# moids2_0_1power.net
KiCad netlist of a schematic drawn in EAGLE
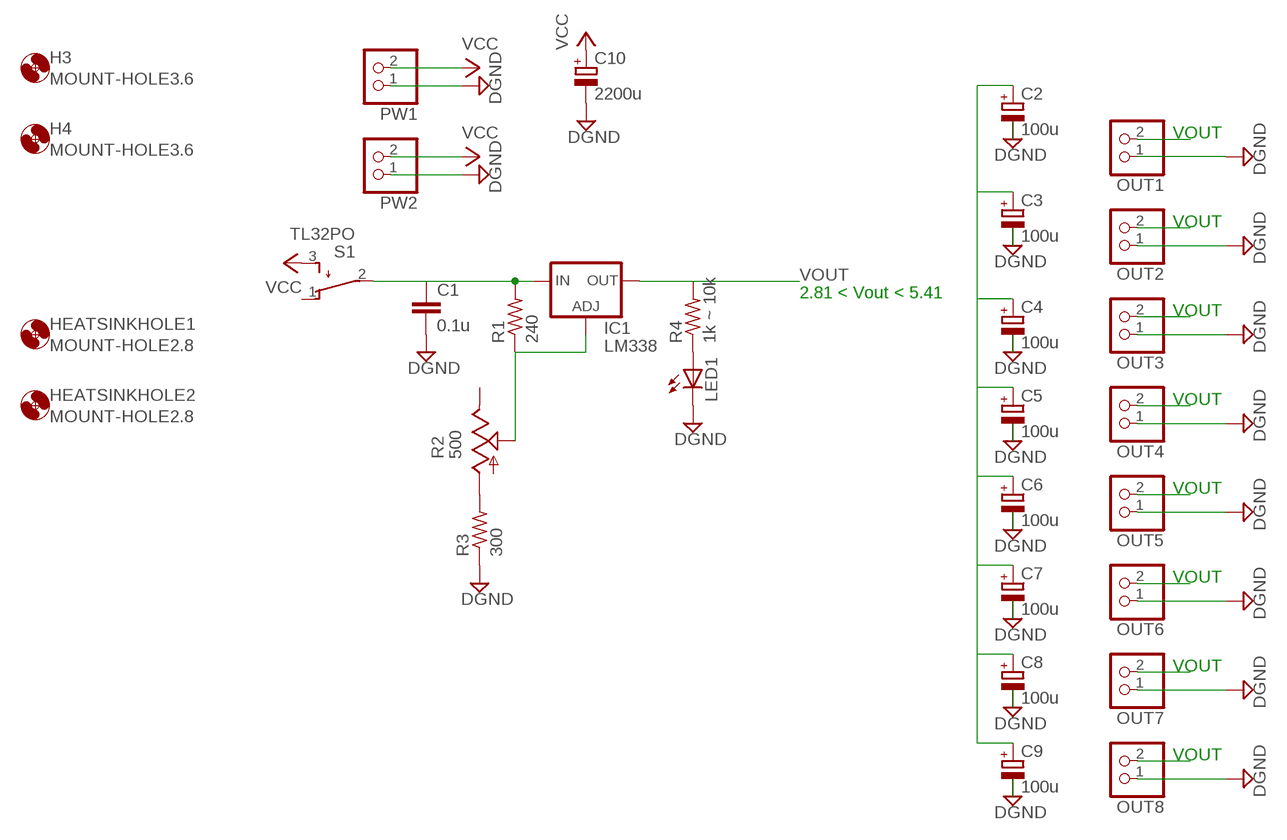
[diagram p0: schematic, sheet 1]

(export (version "E")
  (design (tool "Eeschema 10.0.6"))
  (components
    (comp (ref "C1")
      (value "0.1u")
      (footprint "eagle-import:C025-024X044")
      (libsource (lib "eagle-import") (part "C-EU025-024X044"))
    )
    (comp (ref "C2")
      (value "100u")
      (footprint "eagle-import:E2,5-5")
      (libsource (lib "eagle-import") (part "CPOL-EUE2.5-5"))
    )
    (comp (ref "C3")
      (value "100u")
      (footprint "eagle-import:E2,5-5")
      (libsource (lib "eagle-import") (part "CPOL-EUE2.5-5"))
    )
    (comp (ref "C4")
      (value "100u")
      (footprint "eagle-import:E2,5-5")
      (libsource (lib "eagle-import") (part "CPOL-EUE2.5-5"))
    )
    (comp (ref "C5")
      (value "100u")
      (footprint "eagle-import:E2,5-5")
      (libsource (lib "eagle-import") (part "CPOL-EUE2.5-5"))
    )
    (comp (ref "C6")
      (value "100u")
      (footprint "eagle-import:E2,5-5")
      (libsource (lib "eagle-import") (part "CPOL-EUE2.5-5"))
    )
    (comp (ref "C7")
      (value "100u")
      (footprint "eagle-import:E2,5-5")
      (libsource (lib "eagle-import") (part "CPOL-EUE2.5-5"))
    )
    (comp (ref "C8")
      (value "100u")
      (footprint "eagle-import:E2,5-5")
      (libsource (lib "eagle-import") (part "CPOL-EUE2.5-5"))
    )
    (comp (ref "C9")
      (value "100u")
      (footprint "eagle-import:E2,5-5")
      (libsource (lib "eagle-import") (part "CPOL-EUE2.5-5"))
    )
    (comp (ref "C10")
      (value "2200u")
      (footprint "eagle-import:E7,5-16")
      (libsource (lib "eagle-import") (part "CPOL-EUE7.5-16"))
    )
    (comp (ref "H3")
      (value "MOUNT-HOLE3.6")
      (footprint "eagle-import:3,6")
      (libsource (lib "eagle-import") (part "MOUNT-HOLE3.6"))
    )
    (comp (ref "H4")
      (value "MOUNT-HOLE3.6")
      (footprint "eagle-import:3,6")
      (libsource (lib "eagle-import") (part "MOUNT-HOLE3.6"))
    )
    (comp (ref "HEATSINKHOLE1")
      (value "MOUNT-HOLE2.8")
      (footprint "eagle-import:2,8")
      (libsource (lib "eagle-import") (part "MOUNT-HOLE2.8"))
    )
    (comp (ref "HEATSINKHOLE2")
      (value "MOUNT-HOLE2.8")
      (footprint "eagle-import:2,8")
      (libsource (lib "eagle-import") (part "MOUNT-HOLE2.8"))
    )
    (comp (ref "IC1")
      (value "LM338")
      (footprint "eagle-import:317TS")
      (libsource (lib "eagle-import") (part "LM317TS"))
    )
    (comp (ref "LED1")
      (value "LED3MM")
      (footprint "eagle-import:LED3MM")
      (libsource (lib "eagle-import") (part "LED3MM"))
    )
    (comp (ref "OUT1")
      (value "PINHD-1X2")
      (footprint "eagle-import:1X02")
      (libsource (lib "eagle-import") (part "PINHD-1X2"))
    )
    (comp (ref "OUT2")
      (value "PINHD-1X2")
      (footprint "eagle-import:1X02")
      (libsource (lib "eagle-import") (part "PINHD-1X2"))
    )
    (comp (ref "OUT3")
      (value "PINHD-1X2")
      (footprint "eagle-import:1X02")
      (libsource (lib "eagle-import") (part "PINHD-1X2"))
    )
    (comp (ref "OUT4")
      (value "PINHD-1X2")
      (footprint "eagle-import:1X02")
      (libsource (lib "eagle-import") (part "PINHD-1X2"))
    )
    (comp (ref "OUT5")
      (value "PINHD-1X2")
      (footprint "eagle-import:1X02")
      (libsource (lib "eagle-import") (part "PINHD-1X2"))
    )
    (comp (ref "OUT6")
      (value "PINHD-1X2")
      (footprint "eagle-import:1X02")
      (libsource (lib "eagle-import") (part "PINHD-1X2"))
    )
    (comp (ref "OUT7")
      (value "PINHD-1X2")
      (footprint "eagle-import:1X02")
      (libsource (lib "eagle-import") (part "PINHD-1X2"))
    )
    (comp (ref "OUT8")
      (value "PINHD-1X2")
      (footprint "eagle-import:1X02")
      (libsource (lib "eagle-import") (part "PINHD-1X2"))
    )
    (comp (ref "PW1")
      (value "PINHD-1X2")
      (footprint "eagle-import:1X02")
      (libsource (lib "eagle-import") (part "PINHD-1X2"))
    )
    (comp (ref "PW2")
      (value "PINHD-1X2")
      (footprint "eagle-import:1X02")
      (libsource (lib "eagle-import") (part "PINHD-1X2"))
    )
    (comp (ref "R1")
      (value "240")
      (footprint "eagle-import:0207_2V")
      (libsource (lib "eagle-import") (part "R-US_0207/2V"))
    )
    (comp (ref "R2")
      (value "500")
      (footprint "eagle-import:B25P")
      (libsource (lib "eagle-import") (part "TRIM_US-B25P"))
    )
    (comp (ref "R3")
      (value "300")
      (footprint "eagle-import:0207_2V")
      (libsource (lib "eagle-import") (part "R-US_0207/2V"))
    )
    (comp (ref "R4")
      (value "1k ~ 10k")
      (footprint "eagle-import:0207_2V")
      (libsource (lib "eagle-import") (part "R-US_0207/2V"))
    )
    (comp (ref "S1")
      (value "TL32PO")
      (footprint "eagle-import:TL3XPO")
      (libsource (lib "eagle-import") (part "TL32PO"))
    )
  )
  (nets
    (net (code "1") (name "/VOUT") (class "Default")
      (node (ref "C2") (pin "+") (pinfunction "+_+") (pintype "passive"))
      (node (ref "C3") (pin "+") (pinfunction "+_+") (pintype "passive"))
      (node (ref "C4") (pin "+") (pinfunction "+_+") (pintype "passive"))
      (node (ref "C5") (pin "+") (pinfunction "+_+") (pintype "passive"))
      (node (ref "C6") (pin "+") (pinfunction "+_+") (pintype "passive"))
      (node (ref "C7") (pin "+") (pinfunction "+_+") (pintype "passive"))
      (node (ref "C8") (pin "+") (pinfunction "+_+") (pintype "passive"))
      (node (ref "C9") (pin "+") (pinfunction "+_+") (pintype "passive"))
      (node (ref "IC1") (pin "2") (pinfunction "OUT_2") (pintype "passive"))
      (node (ref "OUT1") (pin "2") (pinfunction "2_2") (pintype "passive"))
      (node (ref "OUT2") (pin "2") (pinfunction "2_2") (pintype "passive"))
      (node (ref "OUT3") (pin "2") (pinfunction "2_2") (pintype "passive"))
      (node (ref "OUT4") (pin "2") (pinfunction "2_2") (pintype "passive"))
      (node (ref "OUT5") (pin "2") (pinfunction "2_2") (pintype "passive"))
      (node (ref "OUT6") (pin "2") (pinfunction "2_2") (pintype "passive"))
      (node (ref "OUT7") (pin "2") (pinfunction "2_2") (pintype "passive"))
      (node (ref "OUT8") (pin "2") (pinfunction "2_2") (pintype "passive"))
      (node (ref "R4") (pin "2") (pinfunction "2_2") (pintype "passive"))
    )
    (net (code "2") (name "DGND") (class "Default")
      (node (ref "C1") (pin "2") (pinfunction "2_2") (pintype "passive"))
      (node (ref "C10") (pin "-") (pinfunction "-_-") (pintype "passive"))
      (node (ref "C2") (pin "-") (pinfunction "-_-") (pintype "passive"))
      (node (ref "C3") (pin "-") (pinfunction "-_-") (pintype "passive"))
      (node (ref "C4") (pin "-") (pinfunction "-_-") (pintype "passive"))
      (node (ref "C5") (pin "-") (pinfunction "-_-") (pintype "passive"))
      (node (ref "C6") (pin "-") (pinfunction "-_-") (pintype "passive"))
      (node (ref "C7") (pin "-") (pinfunction "-_-") (pintype "passive"))
      (node (ref "C8") (pin "-") (pinfunction "-_-") (pintype "passive"))
      (node (ref "C9") (pin "-") (pinfunction "-_-") (pintype "passive"))
      (node (ref "LED1") (pin "K") (pinfunction "C_K") (pintype "passive"))
      (node (ref "OUT1") (pin "1") (pinfunction "1_1") (pintype "passive"))
      (node (ref "OUT2") (pin "1") (pinfunction "1_1") (pintype "passive"))
      (node (ref "OUT3") (pin "1") (pinfunction "1_1") (pintype "passive"))
      (node (ref "OUT4") (pin "1") (pinfunction "1_1") (pintype "passive"))
      (node (ref "OUT5") (pin "1") (pinfunction "1_1") (pintype "passive"))
      (node (ref "OUT6") (pin "1") (pinfunction "1_1") (pintype "passive"))
      (node (ref "OUT7") (pin "1") (pinfunction "1_1") (pintype "passive"))
      (node (ref "OUT8") (pin "1") (pinfunction "1_1") (pintype "passive"))
      (node (ref "PW1") (pin "1") (pinfunction "1_1") (pintype "passive"))
      (node (ref "PW2") (pin "1") (pinfunction "1_1") (pintype "passive"))
      (node (ref "R3") (pin "1") (pinfunction "1_1") (pintype "passive"))
    )
    (net (code "3") (name "Net-(IC1-ADJ)") (class "Default")
      (node (ref "IC1") (pin "1") (pinfunction "ADJ_1") (pintype "input"))
      (node (ref "R1") (pin "1") (pinfunction "1_1") (pintype "passive"))
      (node (ref "R2") (pin "S") (pinfunction "S_S") (pintype "passive"))
    )
    (net (code "4") (name "Net-(IC1-IN)") (class "Default")
      (node (ref "C1") (pin "1") (pinfunction "1_1") (pintype "passive"))
      (node (ref "IC1") (pin "3") (pinfunction "IN_3") (pintype "input"))
      (node (ref "R1") (pin "2") (pinfunction "2_2") (pintype "passive"))
      (node (ref "S1") (pin "2") (pinfunction "P_2") (pintype "passive"))
    )
    (net (code "5") (name "Net-(LED1-PadA)") (class "Default")
      (node (ref "LED1") (pin "A") (pinfunction "A_A") (pintype "passive"))
      (node (ref "R4") (pin "1") (pinfunction "1_1") (pintype "passive"))
    )
    (net (code "6") (name "Net-(R2-PadA)") (class "Default")
      (node (ref "R2") (pin "A") (pinfunction "A_A") (pintype "passive"))
      (node (ref "R3") (pin "2") (pinfunction "2_2") (pintype "passive"))
    )
    (net (code "7") (name "VCC") (class "Default")
      (node (ref "C10") (pin "+") (pinfunction "+_+") (pintype "passive"))
      (node (ref "PW1") (pin "2") (pinfunction "2_2") (pintype "passive"))
      (node (ref "PW2") (pin "2") (pinfunction "2_2") (pintype "passive"))
      (node (ref "S1") (pin "3") (pinfunction "S_3") (pintype "passive"))
    )
    (net (code "8") (name "unconnected-(R2-PadE)") (class "Default")
      (node (ref "R2") (pin "E") (pinfunction "E_E") (pintype "passive"))
    )
    (net (code "9") (name "unconnected-(S1-O-Pad1)") (class "Default")
      (node (ref "S1") (pin "1") (pinfunction "O_1") (pintype "passive"))
    )
  )
)
